# 11-M2_RCB_MUX.net
KiCad netlist of a schematic drawn in Altium Designer
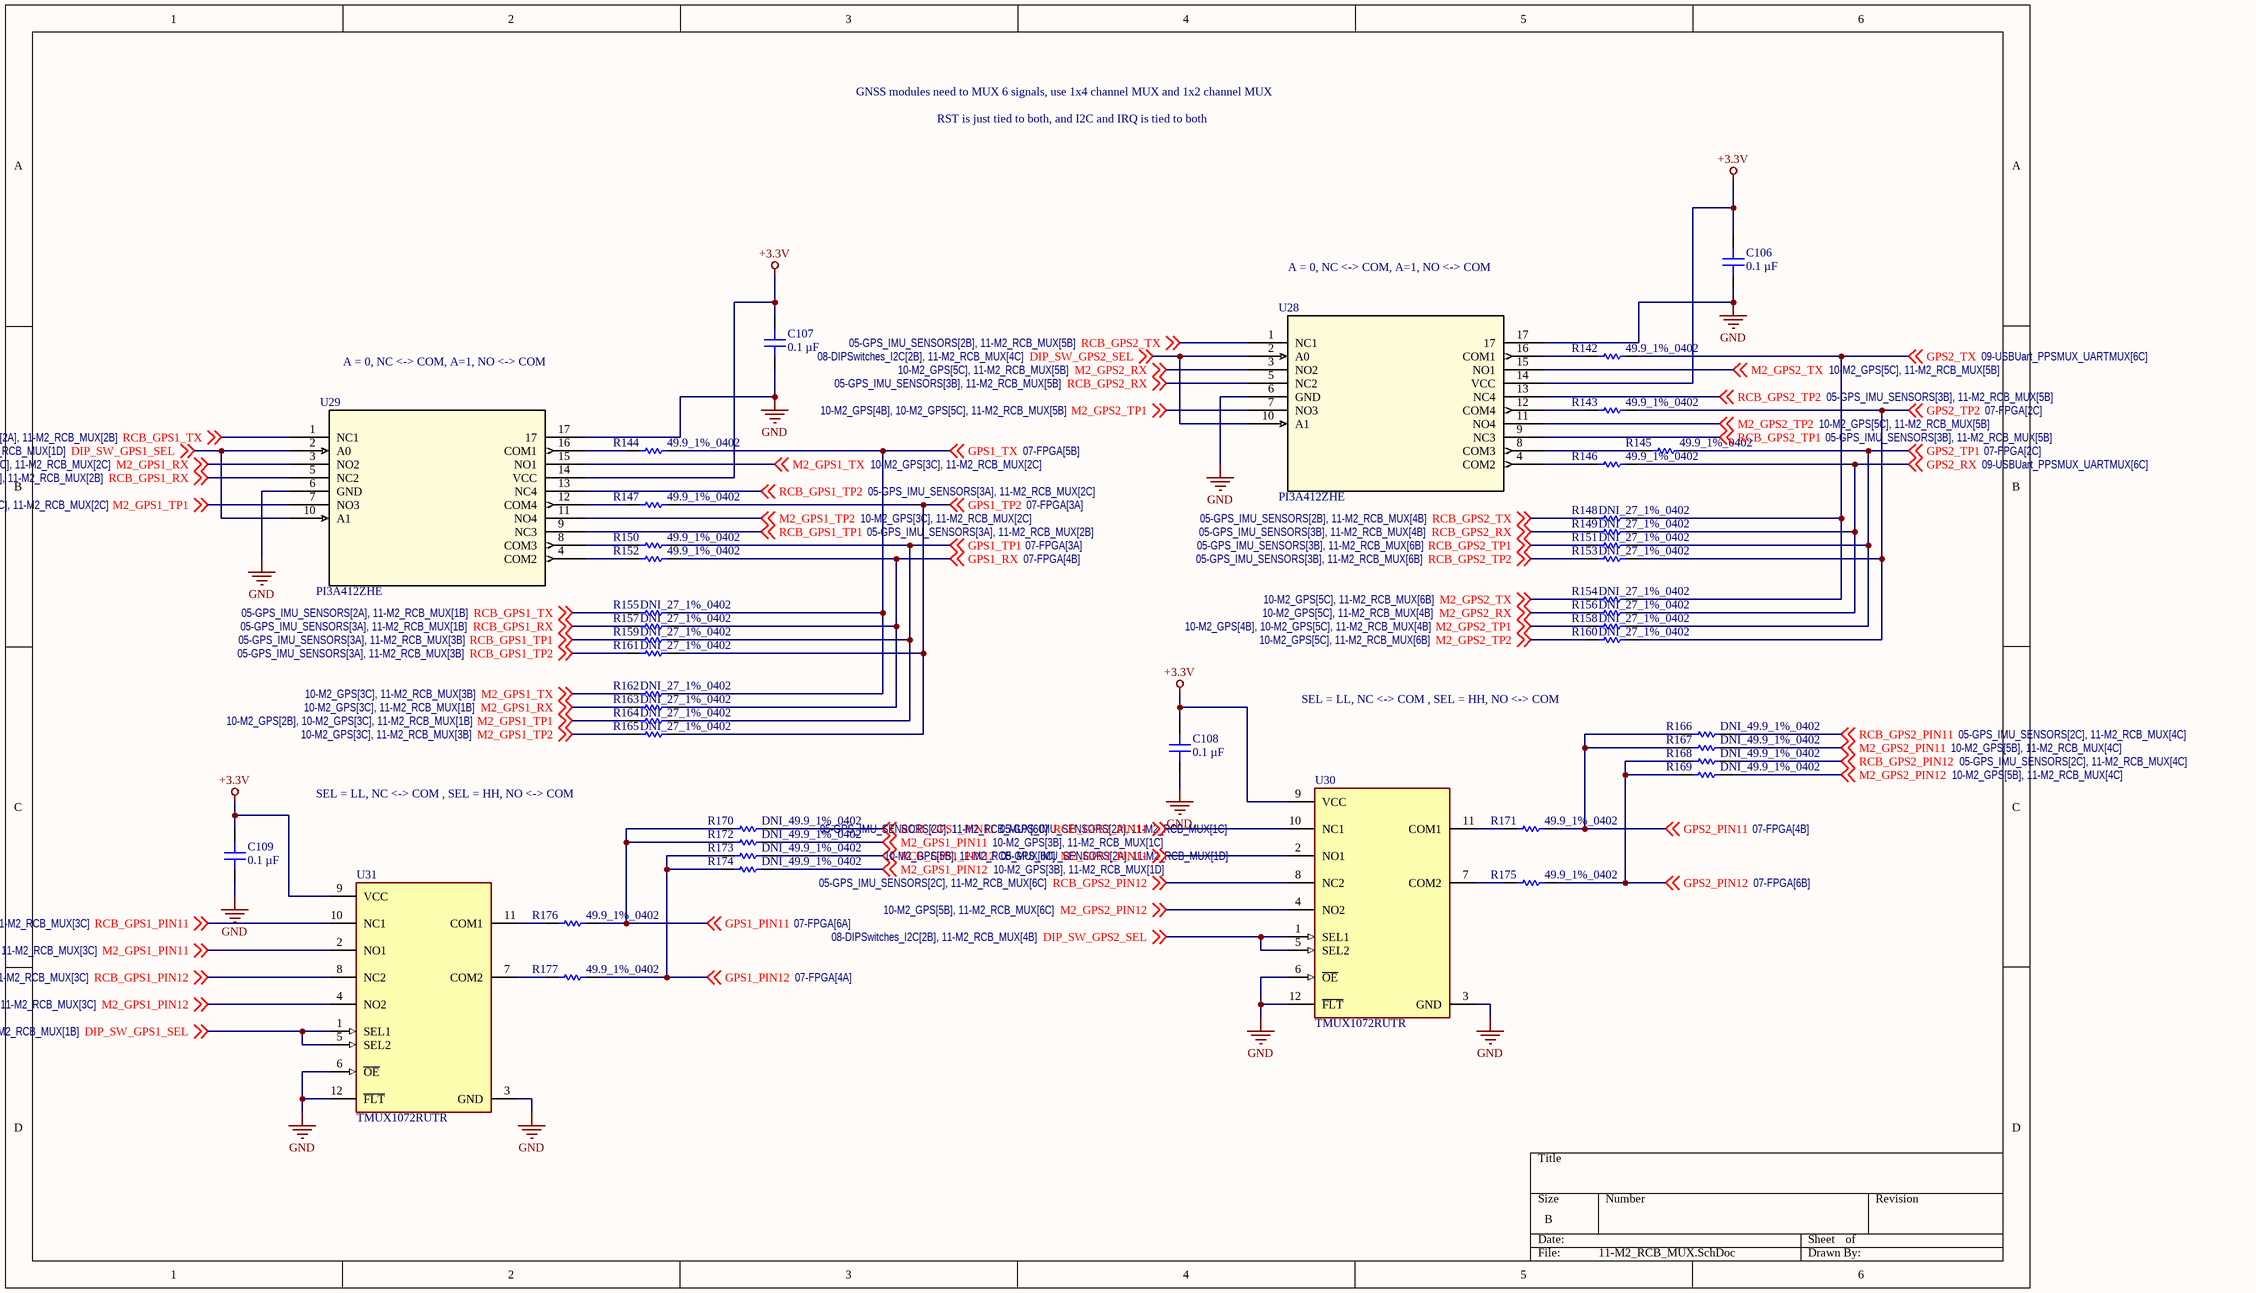
[diagram p0: 11-M2_RCB_MUX.SchDoc]

(export (version "E")
  (design (tool "Eeschema 10.0.6"))
  (components
    (comp (ref "C106")
      (value "0.1 µF")
      (footprint "CAP 0402_1005")
      (description "CAP CER 0.1UF 50V X7R 0402")
      (fields (field (name "TOLERANCE") "±10%") (field (name "PART NUMBER") "CC0402KRX7R9BB104"))
      (libsource (lib "Celestial Altium Library - altium_library") (part "Capacitor"))
    )
    (comp (ref "C107")
      (value "0.1 µF")
      (footprint "CAP 0402_1005")
      (description "CAP CER 0.1UF 50V X7R 0402")
      (fields (field (name "TOLERANCE") "±10%") (field (name "PART NUMBER") "CC0402KRX7R9BB104"))
      (libsource (lib "Celestial Altium Library - altium_library") (part "Capacitor"))
    )
    (comp (ref "C108")
      (value "0.1 µF")
      (footprint "CAP 0402_1005")
      (description "CAP CER 0.1UF 50V X7R 0402")
      (fields (field (name "TOLERANCE") "±10%") (field (name "PART NUMBER") "CC0402KRX7R9BB104"))
      (libsource (lib "Celestial Altium Library - altium_library") (part "Capacitor"))
    )
    (comp (ref "C109")
      (value "0.1 µF")
      (footprint "CAP 0402_1005")
      (description "CAP CER 0.1UF 50V X7R 0402")
      (fields (field (name "TOLERANCE") "±10%") (field (name "PART NUMBER") "CC0402KRX7R9BB104"))
      (libsource (lib "Celestial Altium Library - altium_library") (part "Capacitor"))
    )
    (comp (ref "R142")
      (value "49.9_1%_0402")
      (footprint "RESC1005X40X25LL05T10")
      (fields (field (name "MANUFACTURER") "Yageo / Phycomp") (field (name "PART NUMBER") "RC0402FR-0749R9L"))
      (libsource (lib "Altium Content Vault") (part "RES"))
    )
    (comp (ref "R143")
      (value "49.9_1%_0402")
      (footprint "RESC1005X40X25LL05T10")
      (fields (field (name "MANUFACTURER") "Yageo / Phycomp") (field (name "PART NUMBER") "RC0402FR-0749R9L"))
      (libsource (lib "Altium Content Vault") (part "RES"))
    )
    (comp (ref "R144")
      (value "49.9_1%_0402")
      (footprint "RESC1005X40X25LL05T10")
      (fields (field (name "MANUFACTURER") "Yageo / Phycomp") (field (name "PART NUMBER") "RC0402FR-0749R9L"))
      (libsource (lib "Altium Content Vault") (part "RES"))
    )
    (comp (ref "R145")
      (value "49.9_1%_0402")
      (footprint "RESC1005X40X25LL05T10")
      (fields (field (name "MANUFACTURER") "Yageo / Phycomp") (field (name "PART NUMBER") "RC0402FR-0749R9L"))
      (libsource (lib "Altium Content Vault") (part "RES"))
    )
    (comp (ref "R146")
      (value "49.9_1%_0402")
      (footprint "RESC1005X40X25LL05T10")
      (fields (field (name "MANUFACTURER") "Yageo / Phycomp") (field (name "PART NUMBER") "RC0402FR-0749R9L"))
      (libsource (lib "Altium Content Vault") (part "RES"))
    )
    (comp (ref "R147")
      (value "49.9_1%_0402")
      (footprint "RESC1005X40X25LL05T10")
      (fields (field (name "MANUFACTURER") "Yageo / Phycomp") (field (name "PART NUMBER") "RC0402FR-0749R9L"))
      (libsource (lib "Altium Content Vault") (part "RES"))
    )
    (comp (ref "R148")
      (value "DNI_27_1%_0402")
      (footprint "RESC1005X40X25NL05T05")
      (fields (field (name "PART NUMBER") "CRCW040227R0FKED") (field (name "MANUFACTURER") "Vishay Dale"))
      (libsource (lib "Altium Content Vault") (part "RES"))
    )
    (comp (ref "R149")
      (value "DNI_27_1%_0402")
      (footprint "RESC1005X40X25NL05T05")
      (fields (field (name "PART NUMBER") "CRCW040227R0FKED") (field (name "MANUFACTURER") "Vishay Dale"))
      (libsource (lib "Altium Content Vault") (part "RES"))
    )
    (comp (ref "R150")
      (value "49.9_1%_0402")
      (footprint "RESC1005X40X25LL05T10")
      (fields (field (name "MANUFACTURER") "Yageo / Phycomp") (field (name "PART NUMBER") "RC0402FR-0749R9L"))
      (libsource (lib "Altium Content Vault") (part "RES"))
    )
    (comp (ref "R151")
      (value "DNI_27_1%_0402")
      (footprint "RESC1005X40X25NL05T05")
      (fields (field (name "PART NUMBER") "CRCW040227R0FKED") (field (name "MANUFACTURER") "Vishay Dale"))
      (libsource (lib "Altium Content Vault") (part "RES"))
    )
    (comp (ref "R152")
      (value "49.9_1%_0402")
      (footprint "RESC1005X40X25LL05T10")
      (fields (field (name "MANUFACTURER") "Yageo / Phycomp") (field (name "PART NUMBER") "RC0402FR-0749R9L"))
      (libsource (lib "Altium Content Vault") (part "RES"))
    )
    (comp (ref "R153")
      (value "DNI_27_1%_0402")
      (footprint "RESC1005X40X25NL05T05")
      (fields (field (name "PART NUMBER") "CRCW040227R0FKED") (field (name "MANUFACTURER") "Vishay Dale"))
      (libsource (lib "Altium Content Vault") (part "RES"))
    )
    (comp (ref "R154")
      (value "DNI_27_1%_0402")
      (footprint "RESC1005X40X25NL05T05")
      (fields (field (name "PART NUMBER") "CRCW040227R0FKED") (field (name "MANUFACTURER") "Vishay Dale"))
      (libsource (lib "Altium Content Vault") (part "RES"))
    )
    (comp (ref "R155")
      (value "DNI_27_1%_0402")
      (footprint "RESC1005X40X25NL05T05")
      (fields (field (name "PART NUMBER") "CRCW040227R0FKED") (field (name "MANUFACTURER") "Vishay Dale"))
      (libsource (lib "Altium Content Vault") (part "RES"))
    )
    (comp (ref "R156")
      (value "DNI_27_1%_0402")
      (footprint "RESC1005X40X25NL05T05")
      (fields (field (name "PART NUMBER") "CRCW040227R0FKED") (field (name "MANUFACTURER") "Vishay Dale"))
      (libsource (lib "Altium Content Vault") (part "RES"))
    )
    (comp (ref "R157")
      (value "DNI_27_1%_0402")
      (footprint "RESC1005X40X25NL05T05")
      (fields (field (name "PART NUMBER") "CRCW040227R0FKED") (field (name "MANUFACTURER") "Vishay Dale"))
      (libsource (lib "Altium Content Vault") (part "RES"))
    )
    (comp (ref "R158")
      (value "DNI_27_1%_0402")
      (footprint "RESC1005X40X25NL05T05")
      (fields (field (name "PART NUMBER") "CRCW040227R0FKED") (field (name "MANUFACTURER") "Vishay Dale"))
      (libsource (lib "Altium Content Vault") (part "RES"))
    )
    (comp (ref "R159")
      (value "DNI_27_1%_0402")
      (footprint "RESC1005X40X25NL05T05")
      (fields (field (name "PART NUMBER") "CRCW040227R0FKED") (field (name "MANUFACTURER") "Vishay Dale"))
      (libsource (lib "Altium Content Vault") (part "RES"))
    )
    (comp (ref "R160")
      (value "DNI_27_1%_0402")
      (footprint "RESC1005X40X25NL05T05")
      (fields (field (name "PART NUMBER") "CRCW040227R0FKED") (field (name "MANUFACTURER") "Vishay Dale"))
      (libsource (lib "Altium Content Vault") (part "RES"))
    )
    (comp (ref "R161")
      (value "DNI_27_1%_0402")
      (footprint "RESC1005X40X25NL05T05")
      (fields (field (name "PART NUMBER") "CRCW040227R0FKED") (field (name "MANUFACTURER") "Vishay Dale"))
      (libsource (lib "Altium Content Vault") (part "RES"))
    )
    (comp (ref "R162")
      (value "DNI_27_1%_0402")
      (footprint "RESC1005X40X25NL05T05")
      (fields (field (name "PART NUMBER") "CRCW040227R0FKED") (field (name "MANUFACTURER") "Vishay Dale"))
      (libsource (lib "Altium Content Vault") (part "RES"))
    )
    (comp (ref "R163")
      (value "DNI_27_1%_0402")
      (footprint "RESC1005X40X25NL05T05")
      (fields (field (name "PART NUMBER") "CRCW040227R0FKED") (field (name "MANUFACTURER") "Vishay Dale"))
      (libsource (lib "Altium Content Vault") (part "RES"))
    )
    (comp (ref "R164")
      (value "DNI_27_1%_0402")
      (footprint "RESC1005X40X25NL05T05")
      (fields (field (name "PART NUMBER") "CRCW040227R0FKED") (field (name "MANUFACTURER") "Vishay Dale"))
      (libsource (lib "Altium Content Vault") (part "RES"))
    )
    (comp (ref "R165")
      (value "DNI_27_1%_0402")
      (footprint "RESC1005X40X25NL05T05")
      (fields (field (name "PART NUMBER") "CRCW040227R0FKED") (field (name "MANUFACTURER") "Vishay Dale"))
      (libsource (lib "Altium Content Vault") (part "RES"))
    )
    (comp (ref "R166")
      (value "DNI_49.9_1%_0402")
      (footprint "RESC1005X40X25LL05T10")
      (fields (field (name "MANUFACTURER") "Yageo / Phycomp") (field (name "PART NUMBER") "RC0402FR-0749R9L"))
      (libsource (lib "Altium Content Vault") (part "RES"))
    )
    (comp (ref "R167")
      (value "DNI_49.9_1%_0402")
      (footprint "RESC1005X40X25LL05T10")
      (fields (field (name "MANUFACTURER") "Yageo / Phycomp") (field (name "PART NUMBER") "RC0402FR-0749R9L"))
      (libsource (lib "Altium Content Vault") (part "RES"))
    )
    (comp (ref "R168")
      (value "DNI_49.9_1%_0402")
      (footprint "RESC1005X40X25LL05T10")
      (fields (field (name "MANUFACTURER") "Yageo / Phycomp") (field (name "PART NUMBER") "RC0402FR-0749R9L"))
      (libsource (lib "Altium Content Vault") (part "RES"))
    )
    (comp (ref "R169")
      (value "DNI_49.9_1%_0402")
      (footprint "RESC1005X40X25LL05T10")
      (fields (field (name "MANUFACTURER") "Yageo / Phycomp") (field (name "PART NUMBER") "RC0402FR-0749R9L"))
      (libsource (lib "Altium Content Vault") (part "RES"))
    )
    (comp (ref "R170")
      (value "DNI_49.9_1%_0402")
      (footprint "RESC1005X40X25LL05T10")
      (fields (field (name "MANUFACTURER") "Yageo / Phycomp") (field (name "PART NUMBER") "RC0402FR-0749R9L"))
      (libsource (lib "Altium Content Vault") (part "RES"))
    )
    (comp (ref "R171")
      (value "49.9_1%_0402")
      (footprint "RESC1005X40X25LL05T10")
      (fields (field (name "MANUFACTURER") "Yageo / Phycomp") (field (name "PART NUMBER") "RC0402FR-0749R9L"))
      (libsource (lib "Altium Content Vault") (part "RES"))
    )
    (comp (ref "R172")
      (value "DNI_49.9_1%_0402")
      (footprint "RESC1005X40X25LL05T10")
      (fields (field (name "MANUFACTURER") "Yageo / Phycomp") (field (name "PART NUMBER") "RC0402FR-0749R9L"))
      (libsource (lib "Altium Content Vault") (part "RES"))
    )
    (comp (ref "R173")
      (value "DNI_49.9_1%_0402")
      (footprint "RESC1005X40X25LL05T10")
      (fields (field (name "MANUFACTURER") "Yageo / Phycomp") (field (name "PART NUMBER") "RC0402FR-0749R9L"))
      (libsource (lib "Altium Content Vault") (part "RES"))
    )
    (comp (ref "R174")
      (value "DNI_49.9_1%_0402")
      (footprint "RESC1005X40X25LL05T10")
      (fields (field (name "MANUFACTURER") "Yageo / Phycomp") (field (name "PART NUMBER") "RC0402FR-0749R9L"))
      (libsource (lib "Altium Content Vault") (part "RES"))
    )
    (comp (ref "R175")
      (value "49.9_1%_0402")
      (footprint "RESC1005X40X25LL05T10")
      (fields (field (name "MANUFACTURER") "Yageo / Phycomp") (field (name "PART NUMBER") "RC0402FR-0749R9L"))
      (libsource (lib "Altium Content Vault") (part "RES"))
    )
    (comp (ref "R176")
      (value "49.9_1%_0402")
      (footprint "RESC1005X40X25LL05T10")
      (fields (field (name "MANUFACTURER") "Yageo / Phycomp") (field (name "PART NUMBER") "RC0402FR-0749R9L"))
      (libsource (lib "Altium Content Vault") (part "RES"))
    )
    (comp (ref "R177")
      (value "49.9_1%_0402")
      (footprint "RESC1005X40X25LL05T10")
      (fields (field (name "MANUFACTURER") "Yageo / Phycomp") (field (name "PART NUMBER") "RC0402FR-0749R9L"))
      (libsource (lib "Altium Content Vault") (part "RES"))
    )
    (comp (ref "U28")
      (value "PI3A412ZHE")
      (footprint "ZH16_PER")
      (description "No Description Available")
      (libsource (lib "PI3A412ZHE") (part "PI3A412ZHE"))
    )
    (comp (ref "U29")
      (value "PI3A412ZHE")
      (footprint "ZH16_PER")
      (description "No Description Available")
      (libsource (lib "PI3A412ZHE") (part "PI3A412ZHE"))
    )
    (comp (ref "U30")
      (value "TMUX1072RUTR")
      (footprint "FP-RUT0012A-MFG")
      (description "IC SWITCH SPDT DUAL 12UQFN")
      (libsource (lib "Altium Content Vault") (part "12a319ab100cd6cfe745e35972674f5"))
    )
    (comp (ref "U31")
      (value "TMUX1072RUTR")
      (footprint "FP-RUT0012A-MFG")
      (description "IC SWITCH SPDT DUAL 12UQFN")
      (libsource (lib "Altium Content Vault") (part "12a319ab100cd6cfe745e35972674f5"))
    )
  )
  (nets
    (net (code "1") (name "+3.3V") (class "Default")
      (node (ref "C106") (pin "2") (pinfunction "2_2") (pintype "passive"))
      (node (ref "C107") (pin "2") (pinfunction "2_2") (pintype "passive"))
      (node (ref "C108") (pin "1") (pinfunction "1_1") (pintype "passive"))
      (node (ref "C109") (pin "1") (pinfunction "1_1") (pintype "passive"))
      (node (ref "U28") (pin "14") (pinfunction "VCC_14") (pintype "power_in"))
      (node (ref "U29") (pin "14") (pinfunction "VCC_14") (pintype "power_in"))
      (node (ref "U30") (pin "9") (pinfunction "VCC_9") (pintype "power_in"))
      (node (ref "U31") (pin "9") (pinfunction "VCC_9") (pintype "power_in"))
    )
    (net (code "2") (name "DIP_SW_GPS1_SEL") (class "Default")
      (node (ref "U29") (pin "10") (pinfunction "A1_10") (pintype "input"))
      (node (ref "U29") (pin "2") (pinfunction "A0_2") (pintype "input"))
      (node (ref "U31") (pin "1") (pinfunction "SEL1_1") (pintype "input"))
      (node (ref "U31") (pin "5") (pinfunction "SEL2_5") (pintype "input"))
    )
    (net (code "3") (name "DIP_SW_GPS2_SEL") (class "Default")
      (node (ref "U28") (pin "10") (pinfunction "A1_10") (pintype "input"))
      (node (ref "U28") (pin "2") (pinfunction "A0_2") (pintype "input"))
      (node (ref "U30") (pin "1") (pinfunction "SEL1_1") (pintype "input"))
      (node (ref "U30") (pin "5") (pinfunction "SEL2_5") (pintype "input"))
    )
    (net (code "4") (name "GND") (class "Default")
      (node (ref "C106") (pin "1") (pinfunction "1_1") (pintype "passive"))
      (node (ref "C107") (pin "1") (pinfunction "1_1") (pintype "passive"))
      (node (ref "C108") (pin "2") (pinfunction "2_2") (pintype "passive"))
      (node (ref "C109") (pin "2") (pinfunction "2_2") (pintype "passive"))
      (node (ref "U28") (pin "17") (pinfunction "17_17") (pintype "passive"))
      (node (ref "U28") (pin "6") (pinfunction "GND_6") (pintype "power_in"))
      (node (ref "U29") (pin "17") (pinfunction "17_17") (pintype "passive"))
      (node (ref "U29") (pin "6") (pinfunction "GND_6") (pintype "power_in"))
      (node (ref "U30") (pin "12") (pinfunction "~{FLT}_12") (pintype "open_collector"))
      (node (ref "U30") (pin "3") (pinfunction "GND_3") (pintype "power_in"))
      (node (ref "U30") (pin "6") (pinfunction "~{OE}_6") (pintype "input"))
      (node (ref "U31") (pin "12") (pinfunction "~{FLT}_12") (pintype "open_collector"))
      (node (ref "U31") (pin "3") (pinfunction "GND_3") (pintype "power_in"))
      (node (ref "U31") (pin "6") (pinfunction "~{OE}_6") (pintype "input"))
    )
    (net (code "5") (name "GPS1_PIN11") (class "Default")
      (node (ref "R170") (pin "1") (pinfunction "1_1") (pintype "passive"))
      (node (ref "R172") (pin "1") (pinfunction "1_1") (pintype "passive"))
      (node (ref "R176") (pin "2") (pinfunction "2_2") (pintype "passive"))
    )
    (net (code "6") (name "GPS1_PIN12") (class "Default")
      (node (ref "R173") (pin "1") (pinfunction "1_1") (pintype "passive"))
      (node (ref "R174") (pin "1") (pinfunction "1_1") (pintype "passive"))
      (node (ref "R177") (pin "2") (pinfunction "2_2") (pintype "passive"))
    )
    (net (code "7") (name "GPS1_RX") (class "Default")
      (node (ref "R152") (pin "2") (pinfunction "2_2") (pintype "passive"))
      (node (ref "R157") (pin "2") (pinfunction "2_2") (pintype "passive"))
      (node (ref "R163") (pin "2") (pinfunction "2_2") (pintype "passive"))
    )
    (net (code "8") (name "GPS1_TP1") (class "Default")
      (node (ref "R150") (pin "2") (pinfunction "2_2") (pintype "passive"))
      (node (ref "R159") (pin "2") (pinfunction "2_2") (pintype "passive"))
      (node (ref "R164") (pin "2") (pinfunction "2_2") (pintype "passive"))
    )
    (net (code "9") (name "GPS1_TP2") (class "Default")
      (node (ref "R147") (pin "2") (pinfunction "2_2") (pintype "passive"))
      (node (ref "R161") (pin "2") (pinfunction "2_2") (pintype "passive"))
      (node (ref "R165") (pin "2") (pinfunction "2_2") (pintype "passive"))
    )
    (net (code "10") (name "GPS1_TX") (class "Default")
      (node (ref "R144") (pin "2") (pinfunction "2_2") (pintype "passive"))
      (node (ref "R155") (pin "2") (pinfunction "2_2") (pintype "passive"))
      (node (ref "R162") (pin "2") (pinfunction "2_2") (pintype "passive"))
    )
    (net (code "11") (name "GPS2_PIN11") (class "Default")
      (node (ref "R166") (pin "1") (pinfunction "1_1") (pintype "passive"))
      (node (ref "R167") (pin "1") (pinfunction "1_1") (pintype "passive"))
      (node (ref "R171") (pin "2") (pinfunction "2_2") (pintype "passive"))
    )
    (net (code "12") (name "GPS2_PIN12") (class "Default")
      (node (ref "R168") (pin "1") (pinfunction "1_1") (pintype "passive"))
      (node (ref "R169") (pin "1") (pinfunction "1_1") (pintype "passive"))
      (node (ref "R175") (pin "2") (pinfunction "2_2") (pintype "passive"))
    )
    (net (code "13") (name "GPS2_RX") (class "Default")
      (node (ref "R146") (pin "2") (pinfunction "2_2") (pintype "passive"))
      (node (ref "R149") (pin "2") (pinfunction "2_2") (pintype "passive"))
      (node (ref "R156") (pin "2") (pinfunction "2_2") (pintype "passive"))
    )
    (net (code "14") (name "GPS2_TP1") (class "Default")
      (node (ref "R145") (pin "2") (pinfunction "2_2") (pintype "passive"))
      (node (ref "R151") (pin "2") (pinfunction "2_2") (pintype "passive"))
      (node (ref "R158") (pin "2") (pinfunction "2_2") (pintype "passive"))
    )
    (net (code "15") (name "GPS2_TP2") (class "Default")
      (node (ref "R143") (pin "2") (pinfunction "2_2") (pintype "passive"))
      (node (ref "R153") (pin "2") (pinfunction "2_2") (pintype "passive"))
      (node (ref "R160") (pin "2") (pinfunction "2_2") (pintype "passive"))
    )
    (net (code "16") (name "GPS2_TX") (class "Default")
      (node (ref "R142") (pin "2") (pinfunction "2_2") (pintype "passive"))
      (node (ref "R148") (pin "2") (pinfunction "2_2") (pintype "passive"))
      (node (ref "R154") (pin "2") (pinfunction "2_2") (pintype "passive"))
    )
    (net (code "17") (name "M2_GPS1_PIN11") (class "Default")
      (node (ref "R172") (pin "2") (pinfunction "2_2") (pintype "passive"))
      (node (ref "U31") (pin "2") (pinfunction "NO1_2") (pintype "passive"))
    )
    (net (code "18") (name "M2_GPS1_PIN12") (class "Default")
      (node (ref "R174") (pin "2") (pinfunction "2_2") (pintype "passive"))
      (node (ref "U31") (pin "4") (pinfunction "NO2_4") (pintype "passive"))
    )
    (net (code "19") (name "M2_GPS1_RX") (class "Default")
      (node (ref "R163") (pin "1") (pinfunction "1_1") (pintype "passive"))
      (node (ref "U29") (pin "3") (pinfunction "NO2_3") (pintype "passive"))
    )
    (net (code "20") (name "M2_GPS1_TP1") (class "Default")
      (node (ref "R164") (pin "1") (pinfunction "1_1") (pintype "passive"))
      (node (ref "U29") (pin "7") (pinfunction "NO3_7") (pintype "passive"))
    )
    (net (code "21") (name "M2_GPS1_TP2") (class "Default")
      (node (ref "R165") (pin "1") (pinfunction "1_1") (pintype "passive"))
      (node (ref "U29") (pin "11") (pinfunction "NO4_11") (pintype "passive"))
    )
    (net (code "22") (name "M2_GPS1_TX") (class "Default")
      (node (ref "R162") (pin "1") (pinfunction "1_1") (pintype "passive"))
      (node (ref "U29") (pin "15") (pinfunction "NO1_15") (pintype "passive"))
    )
    (net (code "23") (name "M2_GPS2_PIN11") (class "Default")
      (node (ref "R167") (pin "2") (pinfunction "2_2") (pintype "passive"))
      (node (ref "U30") (pin "2") (pinfunction "NO1_2") (pintype "passive"))
    )
    (net (code "24") (name "M2_GPS2_PIN12") (class "Default")
      (node (ref "R169") (pin "2") (pinfunction "2_2") (pintype "passive"))
      (node (ref "U30") (pin "4") (pinfunction "NO2_4") (pintype "passive"))
    )
    (net (code "25") (name "M2_GPS2_RX") (class "Default")
      (node (ref "R156") (pin "1") (pinfunction "1_1") (pintype "passive"))
      (node (ref "U28") (pin "3") (pinfunction "NO2_3") (pintype "passive"))
    )
    (net (code "26") (name "M2_GPS2_TP1") (class "Default")
      (node (ref "R158") (pin "1") (pinfunction "1_1") (pintype "passive"))
      (node (ref "U28") (pin "7") (pinfunction "NO3_7") (pintype "passive"))
    )
    (net (code "27") (name "M2_GPS2_TP2") (class "Default")
      (node (ref "R160") (pin "1") (pinfunction "1_1") (pintype "passive"))
      (node (ref "U28") (pin "11") (pinfunction "NO4_11") (pintype "passive"))
    )
    (net (code "28") (name "M2_GPS2_TX") (class "Default")
      (node (ref "R154") (pin "1") (pinfunction "1_1") (pintype "passive"))
      (node (ref "U28") (pin "15") (pinfunction "NO1_15") (pintype "passive"))
    )
    (net (code "29") (name "Net-(U28-COM1)") (class "Default")
      (node (ref "R142") (pin "1") (pinfunction "1_1") (pintype "passive"))
      (node (ref "U28") (pin "16") (pinfunction "COM1_16") (pintype "output"))
    )
    (net (code "30") (name "Net-(U28-COM2)") (class "Default")
      (node (ref "R146") (pin "1") (pinfunction "1_1") (pintype "passive"))
      (node (ref "U28") (pin "4") (pinfunction "COM2_4") (pintype "output"))
    )
    (net (code "31") (name "Net-(U28-COM3)") (class "Default")
      (node (ref "R145") (pin "1") (pinfunction "1_1") (pintype "passive"))
      (node (ref "U28") (pin "8") (pinfunction "COM3_8") (pintype "output"))
    )
    (net (code "32") (name "Net-(U28-COM4)") (class "Default")
      (node (ref "R143") (pin "1") (pinfunction "1_1") (pintype "passive"))
      (node (ref "U28") (pin "12") (pinfunction "COM4_12") (pintype "output"))
    )
    (net (code "33") (name "Net-(U29-COM1)") (class "Default")
      (node (ref "R144") (pin "1") (pinfunction "1_1") (pintype "passive"))
      (node (ref "U29") (pin "16") (pinfunction "COM1_16") (pintype "output"))
    )
    (net (code "34") (name "Net-(U29-COM2)") (class "Default")
      (node (ref "R152") (pin "1") (pinfunction "1_1") (pintype "passive"))
      (node (ref "U29") (pin "4") (pinfunction "COM2_4") (pintype "output"))
    )
    (net (code "35") (name "Net-(U29-COM3)") (class "Default")
      (node (ref "R150") (pin "1") (pinfunction "1_1") (pintype "passive"))
      (node (ref "U29") (pin "8") (pinfunction "COM3_8") (pintype "output"))
    )
    (net (code "36") (name "Net-(U29-COM4)") (class "Default")
      (node (ref "R147") (pin "1") (pinfunction "1_1") (pintype "passive"))
      (node (ref "U29") (pin "12") (pinfunction "COM4_12") (pintype "output"))
    )
    (net (code "37") (name "Net-(U30-COM1)") (class "Default")
      (node (ref "R171") (pin "1") (pinfunction "1_1") (pintype "passive"))
      (node (ref "U30") (pin "11") (pinfunction "COM1_11") (pintype "passive"))
    )
    (net (code "38") (name "Net-(U30-COM2)") (class "Default")
      (node (ref "R175") (pin "1") (pinfunction "1_1") (pintype "passive"))
      (node (ref "U30") (pin "7") (pinfunction "COM2_7") (pintype "passive"))
    )
    (net (code "39") (name "Net-(U31-COM1)") (class "Default")
      (node (ref "R176") (pin "1") (pinfunction "1_1") (pintype "passive"))
      (node (ref "U31") (pin "11") (pinfunction "COM1_11") (pintype "passive"))
    )
    (net (code "40") (name "Net-(U31-COM2)") (class "Default")
      (node (ref "R177") (pin "1") (pinfunction "1_1") (pintype "passive"))
      (node (ref "U31") (pin "7") (pinfunction "COM2_7") (pintype "passive"))
    )
    (net (code "41") (name "RCB_GPS1_PIN11") (class "Default")
      (node (ref "R170") (pin "2") (pinfunction "2_2") (pintype "passive"))
      (node (ref "U31") (pin "10") (pinfunction "NC1_10") (pintype "passive"))
    )
    (net (code "42") (name "RCB_GPS1_PIN12") (class "Default")
      (node (ref "R173") (pin "2") (pinfunction "2_2") (pintype "passive"))
      (node (ref "U31") (pin "8") (pinfunction "NC2_8") (pintype "passive"))
    )
    (net (code "43") (name "RCB_GPS1_RX") (class "Default")
      (node (ref "R157") (pin "1") (pinfunction "1_1") (pintype "passive"))
      (node (ref "U29") (pin "5") (pinfunction "NC2_5") (pintype "passive"))
    )
    (net (code "44") (name "RCB_GPS1_TP1") (class "Default")
      (node (ref "R159") (pin "1") (pinfunction "1_1") (pintype "passive"))
      (node (ref "U29") (pin "9") (pinfunction "NC3_9") (pintype "passive"))
    )
    (net (code "45") (name "RCB_GPS1_TP2") (class "Default")
      (node (ref "R161") (pin "1") (pinfunction "1_1") (pintype "passive"))
      (node (ref "U29") (pin "13") (pinfunction "NC4_13") (pintype "passive"))
    )
    (net (code "46") (name "RCB_GPS1_TX") (class "Default")
      (node (ref "R155") (pin "1") (pinfunction "1_1") (pintype "passive"))
      (node (ref "U29") (pin "1") (pinfunction "NC1_1") (pintype "passive"))
    )
    (net (code "47") (name "RCB_GPS2_PIN11") (class "Default")
      (node (ref "R166") (pin "2") (pinfunction "2_2") (pintype "passive"))
      (node (ref "U30") (pin "10") (pinfunction "NC1_10") (pintype "passive"))
    )
    (net (code "48") (name "RCB_GPS2_PIN12") (class "Default")
      (node (ref "R168") (pin "2") (pinfunction "2_2") (pintype "passive"))
      (node (ref "U30") (pin "8") (pinfunction "NC2_8") (pintype "passive"))
    )
    (net (code "49") (name "RCB_GPS2_RX") (class "Default")
      (node (ref "R149") (pin "1") (pinfunction "1_1") (pintype "passive"))
      (node (ref "U28") (pin "5") (pinfunction "NC2_5") (pintype "passive"))
    )
    (net (code "50") (name "RCB_GPS2_TP1") (class "Default")
      (node (ref "R151") (pin "1") (pinfunction "1_1") (pintype "passive"))
      (node (ref "U28") (pin "9") (pinfunction "NC3_9") (pintype "passive"))
    )
    (net (code "51") (name "RCB_GPS2_TP2") (class "Default")
      (node (ref "R153") (pin "1") (pinfunction "1_1") (pintype "passive"))
      (node (ref "U28") (pin "13") (pinfunction "NC4_13") (pintype "passive"))
    )
    (net (code "52") (name "RCB_GPS2_TX") (class "Default")
      (node (ref "R148") (pin "1") (pinfunction "1_1") (pintype "passive"))
      (node (ref "U28") (pin "1") (pinfunction "NC1_1") (pintype "passive"))
    )
  )
)
